# CEU_Camera.net
KiCad netlist of a schematic drawn in Altium Designer
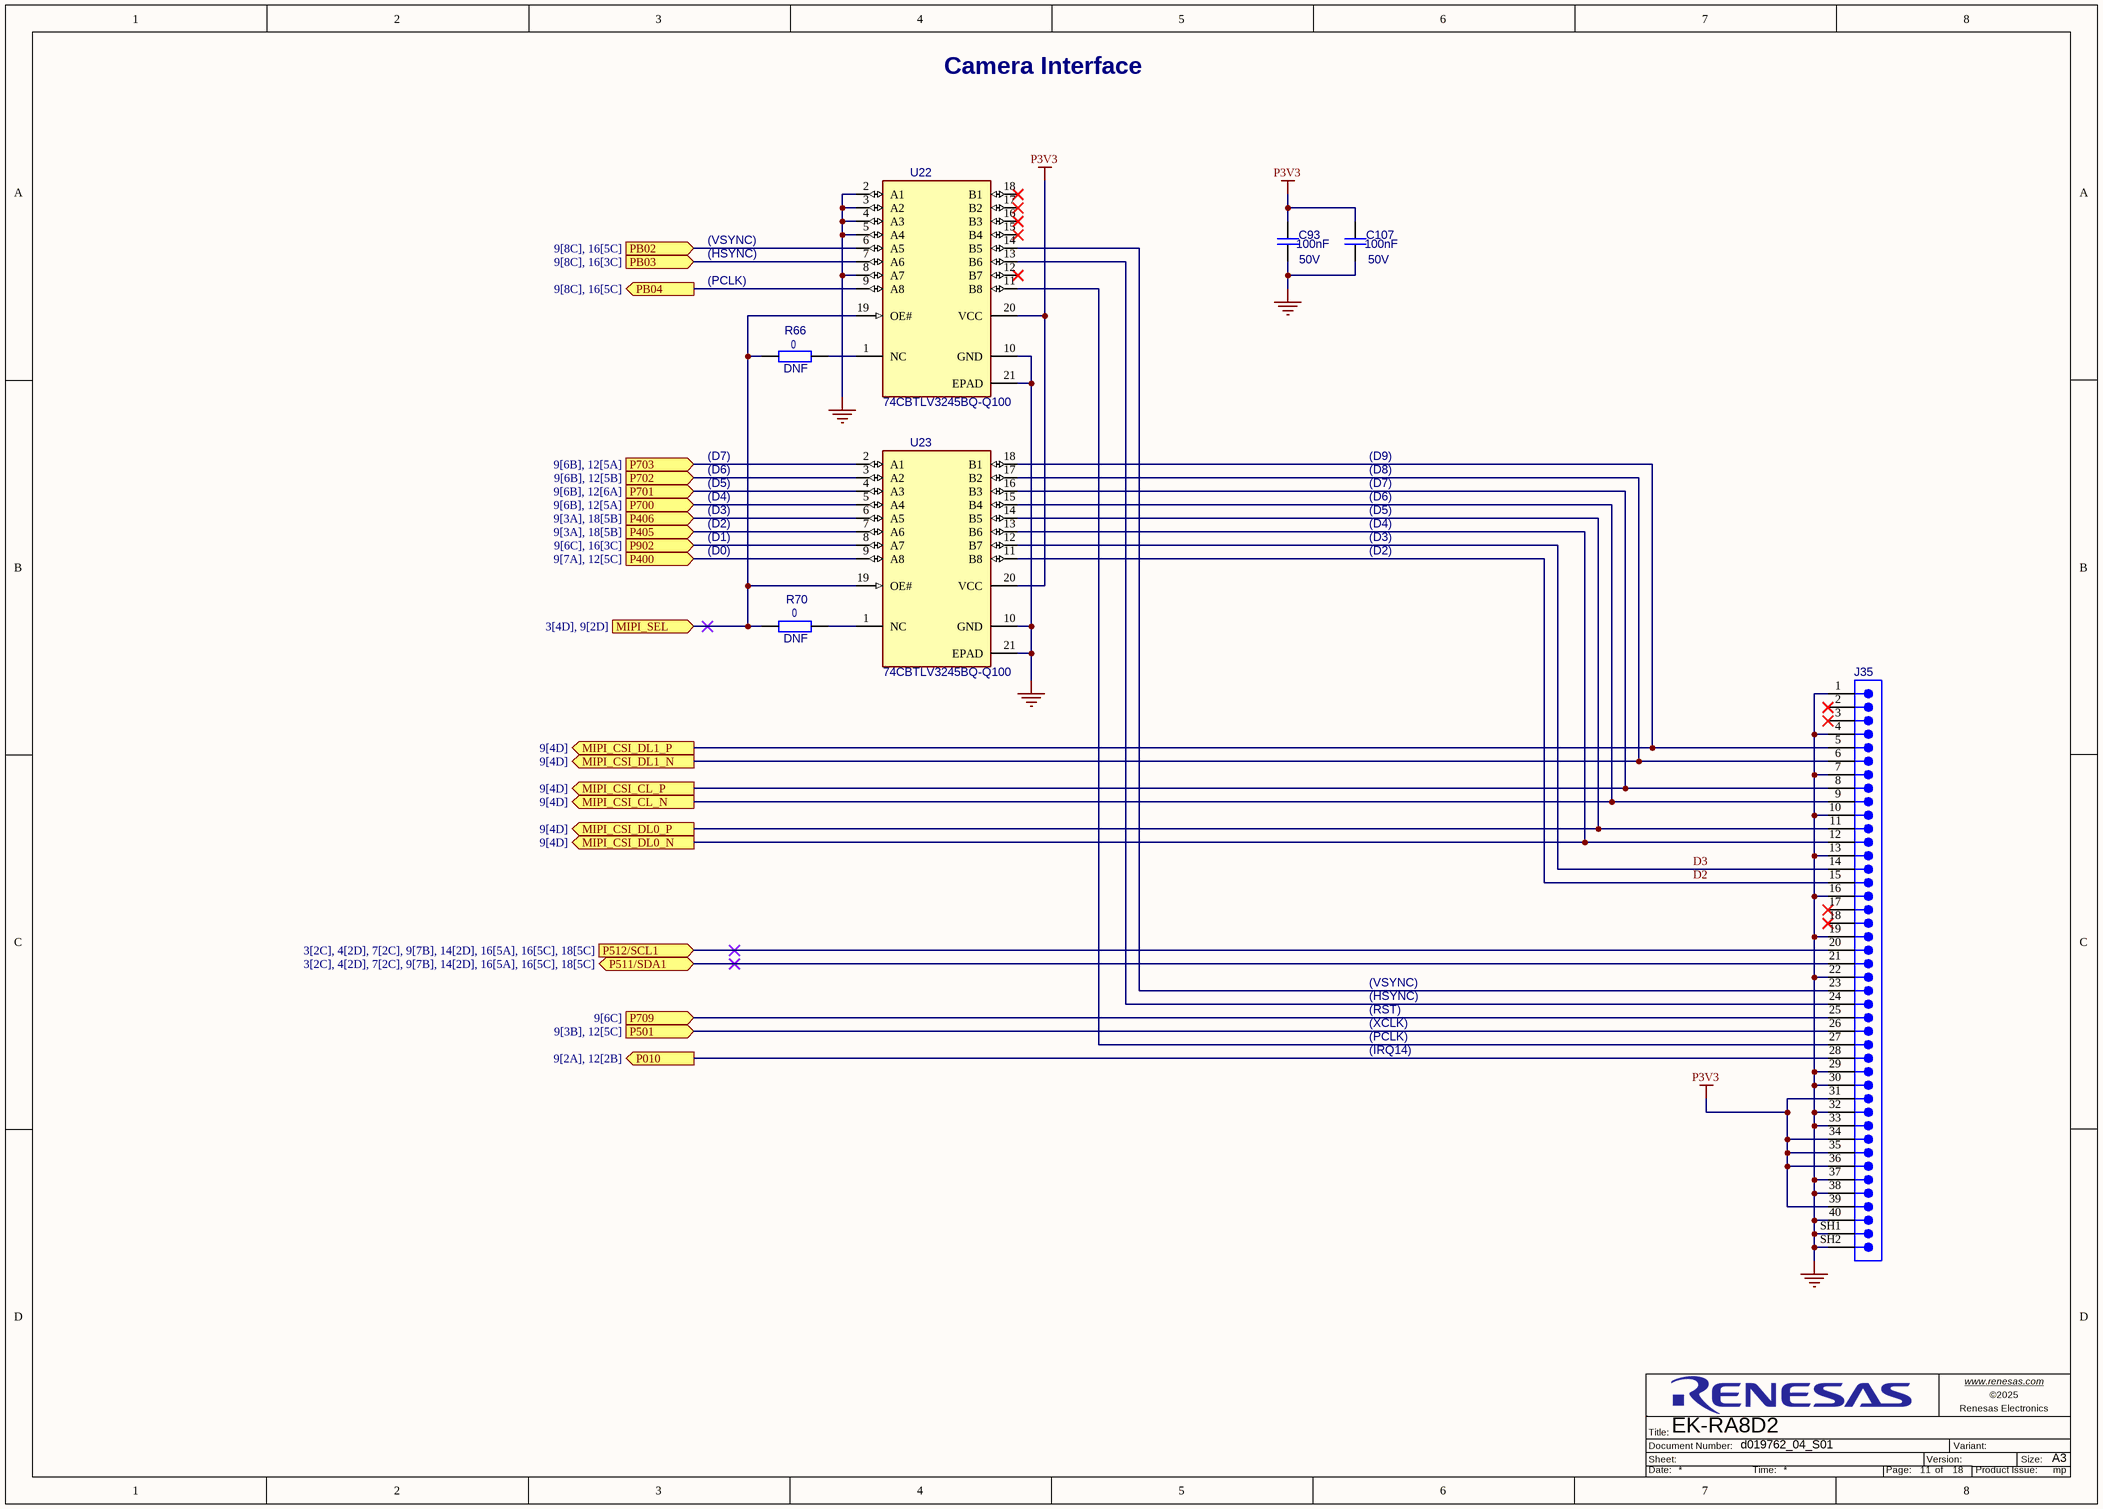
[diagram p0: CEU Camera.SchDoc]

(export (version "E")
  (design (tool "Eeschema 10.0.6"))
  (components
    (comp (ref "C93")
      (value "100nF")
      (footprint "C_EIA0402_0p55")
      (description "Capacitor,EIA0402,100n,50V,X7R")
      (fields
        (field (name "TOLERANCE") "10%")
        (field (name "OPERATING VOLTAGE MAX") "50V")
        (field (name "Comment") "Capacitor")
      )
      (libsource (lib "ek-ra8d2_mp - Customer") (part "Capacitor"))
    )
    (comp (ref "C107")
      (value "100nF")
      (footprint "C_EIA0402_0p55")
      (description "Capacitor,EIA0402,100n,50V,X7R")
      (fields
        (field (name "TOLERANCE") "10%")
        (field (name "OPERATING VOLTAGE MAX") "50V")
        (field (name "Comment") "Capacitor")
      )
      (libsource (lib "ek-ra8d2_mp - Customer") (part "Capacitor"))
    )
    (comp (ref "J35")
      (value "505110-4091")
      (footprint "mol_505110-4091")
      (libsource (lib "ek-ra8d2_mp - Customer") (part "CON_040_MNT2"))
    )
    (comp (ref "R66")
      (value "0")
      (footprint "R_EIA0402")
      (description "Resistor,EIA0402,0,0.0625W")
      (fields (field (name "POWER") "62.5mW") (field (name "TOLERANCE") "5%") (field (name "DNF") "DNF"))
      (libsource (lib "ek-ra8d2_mp - Customer") (part "Resistor"))
    )
    (comp (ref "R70")
      (value "0")
      (footprint "R_EIA0402")
      (description "Resistor,EIA0402,0,0.0625W")
      (fields (field (name "POWER") "62.5mW") (field (name "TOLERANCE") "5%") (field (name "DNF") "DNF"))
      (libsource (lib "ek-ra8d2_mp - Customer") (part "Resistor"))
    )
    (comp (ref "U22")
      (value "74CBTLV3245BQ-Q100")
      (footprint "nex_SOT-764-1_DHVQFN20")
      (description "Octal FET Bus Switch, 5 ohm, 0.3ns max delay, DHVQFN20")
      (libsource (lib "ek-ra8d2_mp - Customer") (part "nex_74CBTLV3245-Q100"))
    )
    (comp (ref "U23")
      (value "74CBTLV3245BQ-Q100")
      (footprint "nex_SOT-764-1_DHVQFN20")
      (description "Octal FET Bus Switch, 5 ohm, 0.3ns max delay, DHVQFN20")
      (libsource (lib "ek-ra8d2_mp - Customer") (part "nex_74CBTLV3245-Q100"))
    )
  )
  (nets
    (net (code "1") (name "/D2") (class "Default")
      (node (ref "J35") (pin "15") (pinfunction "15_15") (pintype "passive"))
      (node (ref "U23") (pin "11") (pinfunction "B8_11") (pintype "bidirectional"))
    )
    (net (code "2") (name "/D3") (class "Default")
      (node (ref "J35") (pin "14") (pinfunction "14_14") (pintype "passive"))
      (node (ref "U23") (pin "12") (pinfunction "B7_12") (pintype "bidirectional"))
    )
    (net (code "3") (name "/MIPI_CSI_CL_N") (class "Default")
      (node (ref "J35") (pin "9") (pinfunction "9_9") (pintype "passive"))
      (node (ref "U23") (pin "15") (pinfunction "B4_15") (pintype "bidirectional"))
    )
    (net (code "4") (name "/MIPI_CSI_CL_P") (class "Default")
      (node (ref "J35") (pin "8") (pinfunction "8_8") (pintype "passive"))
      (node (ref "U23") (pin "16") (pinfunction "B3_16") (pintype "bidirectional"))
    )
    (net (code "5") (name "/MIPI_CSI_DL0_N") (class "Default")
      (node (ref "J35") (pin "12") (pinfunction "12_12") (pintype "passive"))
      (node (ref "U23") (pin "13") (pinfunction "B6_13") (pintype "bidirectional"))
    )
    (net (code "6") (name "/MIPI_CSI_DL0_P") (class "Default")
      (node (ref "J35") (pin "11") (pinfunction "11_11") (pintype "passive"))
      (node (ref "U23") (pin "14") (pinfunction "B5_14") (pintype "bidirectional"))
    )
    (net (code "7") (name "/MIPI_CSI_DL1_N") (class "Default")
      (node (ref "J35") (pin "6") (pinfunction "6_6") (pintype "passive"))
      (node (ref "U23") (pin "17") (pinfunction "B2_17") (pintype "bidirectional"))
    )
    (net (code "8") (name "/MIPI_CSI_DL1_P") (class "Default")
      (node (ref "J35") (pin "5") (pinfunction "5_5") (pintype "passive"))
      (node (ref "U23") (pin "18") (pinfunction "B1_18") (pintype "bidirectional"))
    )
    (net (code "9") (name "/MIPI_SEL") (class "Default")
      (node (ref "R66") (pin "1") (pinfunction "1_1") (pintype "passive"))
      (node (ref "R70") (pin "1") (pinfunction "1_1") (pintype "passive"))
      (node (ref "U22") (pin "19") (pinfunction "OE#_19") (pintype "input"))
      (node (ref "U23") (pin "19") (pinfunction "OE#_19") (pintype "input"))
    )
    (net (code "10") (name "/P010") (class "Default")
      (node (ref "J35") (pin "28") (pinfunction "28_28") (pintype "passive"))
    )
    (net (code "11") (name "/P400") (class "Default")
      (node (ref "U23") (pin "9") (pinfunction "A8_9") (pintype "bidirectional"))
    )
    (net (code "12") (name "/P405") (class "Default")
      (node (ref "U23") (pin "7") (pinfunction "A6_7") (pintype "bidirectional"))
    )
    (net (code "13") (name "/P406") (class "Default")
      (node (ref "U23") (pin "6") (pinfunction "A5_6") (pintype "bidirectional"))
    )
    (net (code "14") (name "/P501") (class "Default")
      (node (ref "J35") (pin "26") (pinfunction "26_26") (pintype "passive"))
    )
    (net (code "15") (name "/P511{slash}SDA1") (class "Default")
      (node (ref "J35") (pin "21") (pinfunction "21_21") (pintype "passive"))
    )
    (net (code "16") (name "/P512{slash}SCL1") (class "Default")
      (node (ref "J35") (pin "20") (pinfunction "20_20") (pintype "passive"))
    )
    (net (code "17") (name "/P700") (class "Default")
      (node (ref "U23") (pin "5") (pinfunction "A4_5") (pintype "bidirectional"))
    )
    (net (code "18") (name "/P701") (class "Default")
      (node (ref "U23") (pin "4") (pinfunction "A3_4") (pintype "bidirectional"))
    )
    (net (code "19") (name "/P702") (class "Default")
      (node (ref "U23") (pin "3") (pinfunction "A2_3") (pintype "bidirectional"))
    )
    (net (code "20") (name "/P703") (class "Default")
      (node (ref "U23") (pin "2") (pinfunction "A1_2") (pintype "bidirectional"))
    )
    (net (code "21") (name "/P709") (class "Default")
      (node (ref "J35") (pin "25") (pinfunction "25_25") (pintype "passive"))
    )
    (net (code "22") (name "/P902") (class "Default")
      (node (ref "U23") (pin "8") (pinfunction "A7_8") (pintype "bidirectional"))
    )
    (net (code "23") (name "/PB02") (class "Default")
      (node (ref "U22") (pin "6") (pinfunction "A5_6") (pintype "bidirectional"))
    )
    (net (code "24") (name "/PB03") (class "Default")
      (node (ref "U22") (pin "7") (pinfunction "A6_7") (pintype "bidirectional"))
    )
    (net (code "25") (name "/PB04") (class "Default")
      (node (ref "U22") (pin "9") (pinfunction "A8_9") (pintype "bidirectional"))
    )
    (net (code "26") (name "GND") (class "Default")
      (node (ref "C107") (pin "1") (pinfunction "1_1") (pintype "passive"))
      (node (ref "C93") (pin "1") (pinfunction "1_1") (pintype "passive"))
      (node (ref "J35") (pin "1") (pinfunction "1_1") (pintype "passive"))
      (node (ref "J35") (pin "10") (pinfunction "10_10") (pintype "passive"))
      (node (ref "J35") (pin "13") (pinfunction "13_13") (pintype "passive"))
      (node (ref "J35") (pin "16") (pinfunction "16_16") (pintype "passive"))
      (node (ref "J35") (pin "19") (pinfunction "19_19") (pintype "passive"))
      (node (ref "J35") (pin "22") (pinfunction "22_22") (pintype "passive"))
      (node (ref "J35") (pin "29") (pinfunction "29_29") (pintype "passive"))
      (node (ref "J35") (pin "30") (pinfunction "30_30") (pintype "passive"))
      (node (ref "J35") (pin "32") (pinfunction "32_32") (pintype "passive"))
      (node (ref "J35") (pin "33") (pinfunction "33_33") (pintype "passive"))
      (node (ref "J35") (pin "37") (pinfunction "37_37") (pintype "passive"))
      (node (ref "J35") (pin "38") (pinfunction "38_38") (pintype "passive"))
      (node (ref "J35") (pin "4") (pinfunction "4_4") (pintype "passive"))
      (node (ref "J35") (pin "40") (pinfunction "40_40") (pintype "passive"))
      (node (ref "J35") (pin "7") (pinfunction "7_7") (pintype "passive"))
      (node (ref "J35") (pin "SH1") (pinfunction "SH1_SH1") (pintype "passive"))
      (node (ref "J35") (pin "SH2") (pinfunction "SH2_SH2") (pintype "passive"))
      (node (ref "U22") (pin "10") (pinfunction "GND_10") (pintype "power_in"))
      (node (ref "U22") (pin "2") (pinfunction "A1_2") (pintype "bidirectional"))
      (node (ref "U22") (pin "21") (pinfunction "EPAD_21") (pintype "power_in"))
      (node (ref "U22") (pin "3") (pinfunction "A2_3") (pintype "bidirectional"))
      (node (ref "U22") (pin "4") (pinfunction "A3_4") (pintype "bidirectional"))
      (node (ref "U22") (pin "5") (pinfunction "A4_5") (pintype "bidirectional"))
      (node (ref "U22") (pin "8") (pinfunction "A7_8") (pintype "bidirectional"))
      (node (ref "U23") (pin "10") (pinfunction "GND_10") (pintype "power_in"))
      (node (ref "U23") (pin "21") (pinfunction "EPAD_21") (pintype "power_in"))
    )
    (net (code "27") (name "Net-(U22-B5)") (class "Default")
      (node (ref "J35") (pin "23") (pinfunction "23_23") (pintype "passive"))
      (node (ref "U22") (pin "14") (pinfunction "B5_14") (pintype "bidirectional"))
    )
    (net (code "28") (name "Net-(U22-B6)") (class "Default")
      (node (ref "J35") (pin "24") (pinfunction "24_24") (pintype "passive"))
      (node (ref "U22") (pin "13") (pinfunction "B6_13") (pintype "bidirectional"))
    )
    (net (code "29") (name "Net-(U22-B8)") (class "Default")
      (node (ref "J35") (pin "27") (pinfunction "27_27") (pintype "passive"))
      (node (ref "U22") (pin "11") (pinfunction "B8_11") (pintype "bidirectional"))
    )
    (net (code "30") (name "Net-(U22-NC)") (class "Default")
      (node (ref "R66") (pin "2") (pinfunction "2_2") (pintype "passive"))
      (node (ref "U22") (pin "1") (pinfunction "NC_1") (pintype "passive"))
    )
    (net (code "31") (name "Net-(U23-NC)") (class "Default")
      (node (ref "R70") (pin "2") (pinfunction "2_2") (pintype "passive"))
      (node (ref "U23") (pin "1") (pinfunction "NC_1") (pintype "passive"))
    )
    (net (code "32") (name "P3V3") (class "Default")
      (node (ref "C107") (pin "2") (pinfunction "2_2") (pintype "passive"))
      (node (ref "C93") (pin "2") (pinfunction "2_2") (pintype "passive"))
      (node (ref "J35") (pin "31") (pinfunction "31_31") (pintype "passive"))
      (node (ref "J35") (pin "34") (pinfunction "34_34") (pintype "passive"))
      (node (ref "J35") (pin "35") (pinfunction "36_35") (pintype "passive"))
      (node (ref "J35") (pin "36") (pinfunction "36_36") (pintype "passive"))
      (node (ref "J35") (pin "39") (pinfunction "39_39") (pintype "passive"))
      (node (ref "U22") (pin "20") (pinfunction "VCC_20") (pintype "power_in"))
      (node (ref "U23") (pin "20") (pinfunction "VCC_20") (pintype "power_in"))
    )
    (net (code "33") (name "unconnected-(J35-Pad2)") (class "Default")
      (node (ref "J35") (pin "2") (pinfunction "2_2") (pintype "passive+no_connect"))
    )
    (net (code "34") (name "unconnected-(J35-Pad3)") (class "Default")
      (node (ref "J35") (pin "3") (pinfunction "3_3") (pintype "passive+no_connect"))
    )
    (net (code "35") (name "unconnected-(J35-Pad17)") (class "Default")
      (node (ref "J35") (pin "17") (pinfunction "17_17") (pintype "passive+no_connect"))
    )
    (net (code "36") (name "unconnected-(J35-Pad18)") (class "Default")
      (node (ref "J35") (pin "18") (pinfunction "18_18") (pintype "passive+no_connect"))
    )
    (net (code "37") (name "unconnected-(U22-B1-Pad18)") (class "Default")
      (node (ref "U22") (pin "18") (pinfunction "B1_18") (pintype "bidirectional+no_connect"))
    )
    (net (code "38") (name "unconnected-(U22-B2-Pad17)") (class "Default")
      (node (ref "U22") (pin "17") (pinfunction "B2_17") (pintype "bidirectional+no_connect"))
    )
    (net (code "39") (name "unconnected-(U22-B3-Pad16)") (class "Default")
      (node (ref "U22") (pin "16") (pinfunction "B3_16") (pintype "bidirectional+no_connect"))
    )
    (net (code "40") (name "unconnected-(U22-B4-Pad15)") (class "Default")
      (node (ref "U22") (pin "15") (pinfunction "B4_15") (pintype "bidirectional+no_connect"))
    )
    (net (code "41") (name "unconnected-(U22-B7-Pad12)") (class "Default")
      (node (ref "U22") (pin "12") (pinfunction "B7_12") (pintype "bidirectional+no_connect"))
    )
  )
)
